# Master_Micro_Controller_Core.net
KiCad netlist of a schematic drawn in Altium Designer
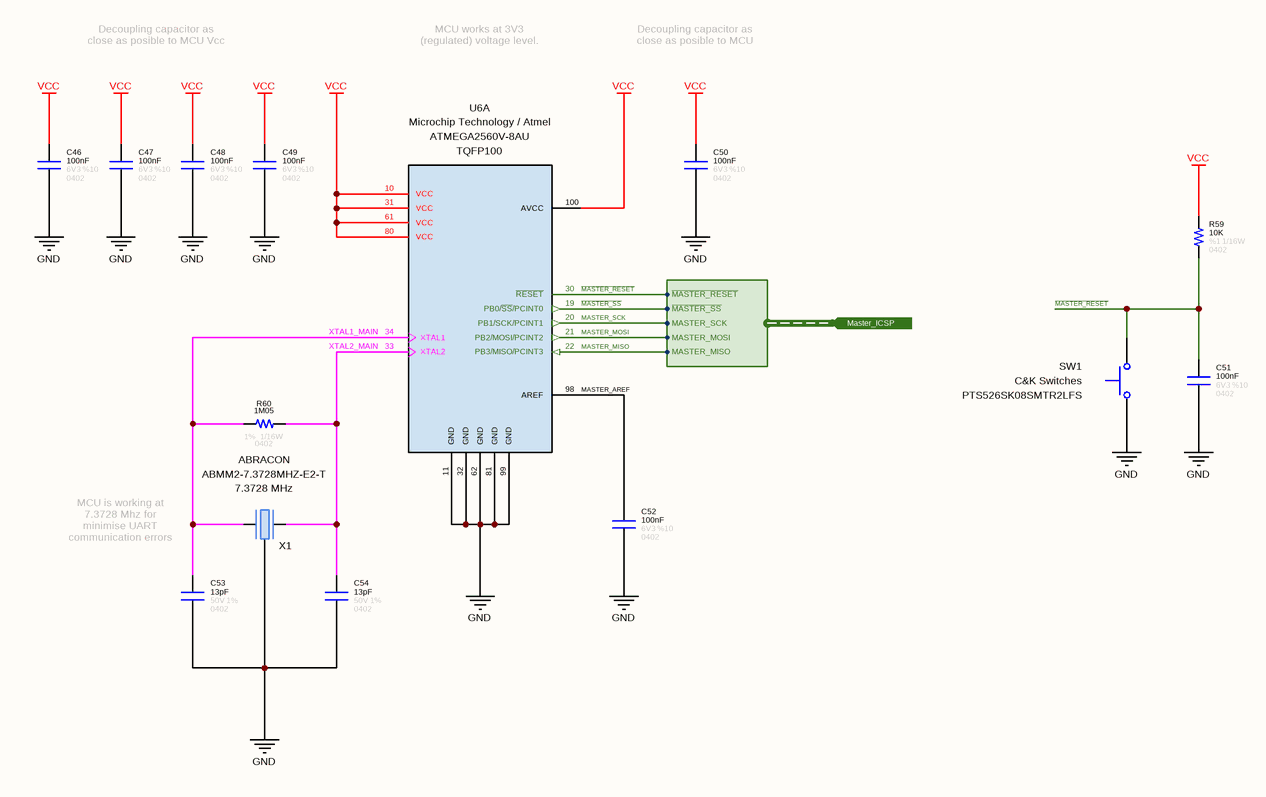
[diagram p0: Master Micro Controller Core.SchDoc]

(export (version "E")
  (design (tool "Eeschema 10.0.6"))
  (components
    (comp (ref "C46")
      (value "100nF")
      (footprint "CAPACITOR_0402")
      (description "Capacitor - 100nF [0402-6V3] (Ceramic)")
      (fields
        (field (name "MANUFACTURER PART NUMBER") "04026D104KAT4A")
        (field (name "TOLERANCE") "%10")
        (field (name "VOLTAGE") "6V3")
        (field (name "CASE") "0402")
        (field (name "Comment") "Capacitor - 100nF [0402] (Ceramic)")
      )
      (libsource (lib "P101DA_Library") (part "Capacitor - 100nF [0402-6V3]"))
    )
    (comp (ref "C47")
      (value "100nF")
      (footprint "CAPACITOR_0402")
      (description "Capacitor - 100nF [0402-6V3] (Ceramic)")
      (fields
        (field (name "MANUFACTURER PART NUMBER") "04026D104KAT4A")
        (field (name "TOLERANCE") "%10")
        (field (name "VOLTAGE") "6V3")
        (field (name "CASE") "0402")
        (field (name "Comment") "Capacitor - 100nF [0402] (Ceramic)")
      )
      (libsource (lib "P101DA_Library") (part "Capacitor - 100nF [0402-6V3]"))
    )
    (comp (ref "C48")
      (value "100nF")
      (footprint "CAPACITOR_0402")
      (description "Capacitor - 100nF [0402-6V3] (Ceramic)")
      (fields
        (field (name "MANUFACTURER PART NUMBER") "04026D104KAT4A")
        (field (name "TOLERANCE") "%10")
        (field (name "VOLTAGE") "6V3")
        (field (name "CASE") "0402")
        (field (name "Comment") "Capacitor - 100nF [0402] (Ceramic)")
      )
      (libsource (lib "P101DA_Library") (part "Capacitor - 100nF [0402-6V3]"))
    )
    (comp (ref "C49")
      (value "100nF")
      (footprint "CAPACITOR_0402")
      (description "Capacitor - 100nF [0402-6V3] (Ceramic)")
      (fields
        (field (name "MANUFACTURER PART NUMBER") "04026D104KAT4A")
        (field (name "TOLERANCE") "%10")
        (field (name "VOLTAGE") "6V3")
        (field (name "CASE") "0402")
        (field (name "Comment") "Capacitor - 100nF [0402] (Ceramic)")
      )
      (libsource (lib "P101DA_Library") (part "Capacitor - 100nF [0402-6V3]"))
    )
    (comp (ref "C50")
      (value "100nF")
      (footprint "CAPACITOR_0402")
      (description "Capacitor - 100nF [0402-6V3] (Ceramic)")
      (fields
        (field (name "MANUFACTURER PART NUMBER") "04026D104KAT4A")
        (field (name "TOLERANCE") "%10")
        (field (name "VOLTAGE") "6V3")
        (field (name "CASE") "0402")
        (field (name "Comment") "Capacitor - 100nF [0402] (Ceramic)")
      )
      (libsource (lib "P101DA_Library") (part "Capacitor - 100nF [0402-6V3]"))
    )
    (comp (ref "C51")
      (value "100nF")
      (footprint "CAPACITOR_0402")
      (description "Capacitor - 100nF [0402-6V3] (Ceramic)")
      (fields
        (field (name "MANUFACTURER PART NUMBER") "04026D104KAT4A")
        (field (name "TOLERANCE") "%10")
        (field (name "VOLTAGE") "6V3")
        (field (name "CASE") "0402")
        (field (name "Comment") "Capacitor - 100nF [0402] (Ceramic)")
      )
      (libsource (lib "P101DA_Library") (part "Capacitor - 100nF [0402-6V3]"))
    )
    (comp (ref "C52")
      (value "100nF")
      (footprint "CAPACITOR_0402")
      (description "Capacitor - 100nF [0402-6V3] (Ceramic)")
      (fields
        (field (name "MANUFACTURER PART NUMBER") "04026D104KAT4A")
        (field (name "TOLERANCE") "%10")
        (field (name "VOLTAGE") "6V3")
        (field (name "CASE") "0402")
        (field (name "Comment") "Capacitor - 100nF [0402] (Ceramic)")
      )
      (libsource (lib "P101DA_Library") (part "Capacitor - 100nF [0402-6V3]"))
    )
    (comp (ref "C53")
      (value "13pF")
      (footprint "CAPACITOR_0402")
      (description "Multilayer Ceramic Capacitors - SMD - 50V 13pF X5R 0402 1%")
      (fields
        (field (name "MANUFACTURER PART NUMBER") "CBR04C130F5GAC")
        (field (name "TOLERANCE") "1%")
        (field (name "CASE") "0402")
        (field (name "VOLTAGE") "50V")
        (field (name "Comment") "Capacitor - 13pF [0402] (Ceramic)")
      )
      (libsource (lib "P101DA_Library") (part "Capacitor - 13pF [0402-50V]"))
    )
    (comp (ref "C54")
      (value "13pF")
      (footprint "CAPACITOR_0402")
      (description "Multilayer Ceramic Capacitors - SMD - 50V 13pF X5R 0402 1%")
      (fields
        (field (name "MANUFACTURER PART NUMBER") "CBR04C130F5GAC")
        (field (name "TOLERANCE") "1%")
        (field (name "CASE") "0402")
        (field (name "VOLTAGE") "50V")
        (field (name "Comment") "Capacitor - 13pF [0402] (Ceramic)")
      )
      (libsource (lib "P101DA_Library") (part "Capacitor - 13pF [0402-50V]"))
    )
    (comp (ref "R59")
      (value "10K")
      (footprint "RESISTOR_0402")
      (description "Thick Film Resistors - SMD 1/16 W 10 KOhm 1%")
      (fields
        (field (name "MANUFACTURER PART NUMBER") "CRCW040210K0FKED")
        (field (name "TOLERANCE") "%1")
        (field (name "CASE") "0402")
        (field (name "POWER") "1/16W")
        (field (name "Comment") "10K - 0402 - %1 - 1/16W")
      )
      (libsource (lib "P101DA_Library") (part "Resistor - 10K [0402]"))
    )
    (comp (ref "R60")
      (value "1M05")
      (footprint "RESISTOR_0402")
      (description "Thick Film Resistors - SMD 1/16 W 1.05 MOhm 1%")
      (fields
        (field (name "MANUFACTURER PART NUMBER") "CRCW04021M05FKED")
        (field (name "POWER") "1/16W")
        (field (name "CASE") "0402")
        (field (name "TOLERANCE") "1%")
        (field (name "Comment") "1M05 - 0402 - %1 - 1/16W")
      )
      (libsource (lib "P101DA_Library") (part "Resistor - 1M05 [0402]"))
    )
    (comp (ref "SW1")
      (value "PTS526SK08SMTR2LFS")
      (footprint "PTS526_Switch")
      (description "Switch Tactile N.O. SPST Flush Round Button Gull Wing 0.05A 12VDC 200000Cycles 2.45N SMD T/R")
      (fields
        (field (name "MANUFACTURER NAME") "C&K Switches")
        (field (name "MANUFACTURER PART NUMBER") "PTS526SK08SMTR2LFS")
      )
      (libsource (lib "P101DA_Library") (part "Switch - Push Button"))
    )
    (comp (ref "U6")
      (value "ATMEGA2560V-8AU")
      (footprint "TQFP-100")
      (description "ATmega Series 256 KB Flash 8 KB SRAM 8 MHz 8-Bit Microcontroller - TQFP-100")
      (fields
        (field (name "MANUFACTURER NAME") "Microchip Technology / Atmel")
        (field (name "MANUFACTURER PART NUMBER") "ATMEGA2560V-8AU")
        (field (name "CASE") "TQFP100")
      )
      (libsource (lib "P101DA_Library") (part "IC - AtMega2560V-8AU"))
    )
    (comp (ref "X1")
      (value "ABMM2-7.3728MHZ-E2-T")
      (footprint "CRYSTAL - 7.3728 MHz")
      (description "CRYSTAL 7.3728MHZ 18PF SMD")
      (fields
        (field (name "MANUFACTURER NAME") "ABRACON")
        (field (name "MANUFACTURER PART NUMBER") "ABMM2-7.3728MHZ-E2-T")
        (field (name "FREQUENCY") "7.3728 MHz")
      )
      (libsource (lib "P101DA_Library") (part "Crystal - 7.3728MHz"))
    )
  )
  (nets
    (net (code "2") (name "/MASTER_AREF") (class "Default")
      (node (ref "C52") (pin "2") (pinfunction "2_2") (pintype "passive"))
      (node (ref "U6") (pin "98") (pinfunction "AREF_98") (pintype "passive"))
    )
    (net (code "3") (name "/MASTER_MISO") (class "Default")
      (node (ref "U6") (pin "22") (pinfunction "PB3/MISO/PCINT3_22") (pintype "input"))
    )
    (net (code "4") (name "/MASTER_MOSI") (class "Default")
      (node (ref "U6") (pin "21") (pinfunction "PB2/MOSI/PCINT2_21") (pintype "output"))
    )
    (net (code "5") (name "/MASTER_SCK") (class "Default")
      (node (ref "U6") (pin "20") (pinfunction "PB1/SCK/PCINT1_20") (pintype "output"))
    )
    (net (code "6") (name "/XTAL1_MAIN") (class "Default")
      (node (ref "C53") (pin "2") (pinfunction "2_2") (pintype "passive"))
      (node (ref "R60") (pin "1") (pinfunction "1_1") (pintype "passive"))
      (node (ref "U6") (pin "34") (pinfunction "XTAL1_34") (pintype "passive"))
      (node (ref "X1") (pin "3") (pinfunction "OUT/IN_3") (pintype "passive"))
    )
    (net (code "7") (name "/XTAL2_MAIN") (class "Default")
      (node (ref "C54") (pin "2") (pinfunction "2_2") (pintype "passive"))
      (node (ref "R60") (pin "2") (pinfunction "2_2") (pintype "passive"))
      (node (ref "U6") (pin "33") (pinfunction "XTAL2_33") (pintype "passive"))
      (node (ref "X1") (pin "1") (pinfunction "IN/OUT_1") (pintype "passive"))
    )
    (net (code "9") (name "/~{MASTER_RESET}") (class "Default")
      (node (ref "C51") (pin "2") (pinfunction "2_2") (pintype "passive"))
      (node (ref "R59") (pin "1") (pinfunction "1_1") (pintype "passive"))
      (node (ref "SW1") (pin "2") (pinfunction "COM_2") (pintype "passive"))
      (node (ref "U6") (pin "30") (pinfunction "~{RESET}_30") (pintype "passive"))
    )
    (net (code "10") (name "/~{MASTER_SS}") (class "Default")
      (node (ref "U6") (pin "19") (pinfunction "PB0/~{SS}/PCINT0_19") (pintype "output"))
    )
    (net (code "11") (name "GND") (class "Default")
      (node (ref "C46") (pin "1") (pinfunction "1_1") (pintype "passive"))
      (node (ref "C47") (pin "1") (pinfunction "1_1") (pintype "passive"))
      (node (ref "C48") (pin "1") (pinfunction "1_1") (pintype "passive"))
      (node (ref "C49") (pin "1") (pinfunction "1_1") (pintype "passive"))
      (node (ref "C50") (pin "1") (pinfunction "1_1") (pintype "passive"))
      (node (ref "C51") (pin "1") (pinfunction "1_1") (pintype "passive"))
      (node (ref "C52") (pin "1") (pinfunction "1_1") (pintype "passive"))
      (node (ref "C53") (pin "1") (pinfunction "1_1") (pintype "passive"))
      (node (ref "C54") (pin "1") (pinfunction "1_1") (pintype "passive"))
      (node (ref "SW1") (pin "1") (pinfunction "NC_1") (pintype "passive"))
      (node (ref "U6") (pin "11") (pinfunction "GND_11") (pintype "passive"))
      (node (ref "U6") (pin "32") (pinfunction "GND_32") (pintype "passive"))
      (node (ref "U6") (pin "62") (pinfunction "GND_62") (pintype "passive"))
      (node (ref "U6") (pin "81") (pinfunction "GND_81") (pintype "passive"))
      (node (ref "U6") (pin "99") (pinfunction "GND_99") (pintype "passive"))
      (node (ref "X1") (pin "2") (pinfunction "GND_2") (pintype "passive"))
    )
    (net (code "12") (name "VCC") (class "Default")
      (node (ref "C46") (pin "2") (pinfunction "2_2") (pintype "passive"))
      (node (ref "C47") (pin "2") (pinfunction "2_2") (pintype "passive"))
      (node (ref "C48") (pin "2") (pinfunction "2_2") (pintype "passive"))
      (node (ref "C49") (pin "2") (pinfunction "2_2") (pintype "passive"))
      (node (ref "C50") (pin "2") (pinfunction "2_2") (pintype "passive"))
      (node (ref "R59") (pin "2") (pinfunction "2_2") (pintype "passive"))
      (node (ref "U6") (pin "10") (pinfunction "VCC_10") (pintype "power_in"))
      (node (ref "U6") (pin "100") (pinfunction "AVCC_100") (pintype "passive"))
      (node (ref "U6") (pin "31") (pinfunction "VCC_31") (pintype "power_in"))
      (node (ref "U6") (pin "61") (pinfunction "VCC_61") (pintype "power_in"))
      (node (ref "U6") (pin "80") (pinfunction "VCC_80") (pintype "power_in"))
    )
    (net (code "13") (name "unconnected-(X1-GND-Pad4)") (class "Default")
      (node (ref "X1") (pin "4") (pinfunction "GND_4") (pintype "passive"))
    )
  )
)
